# distribution-puissance.net
KiCad netlist of a schematic drawn in EAGLE
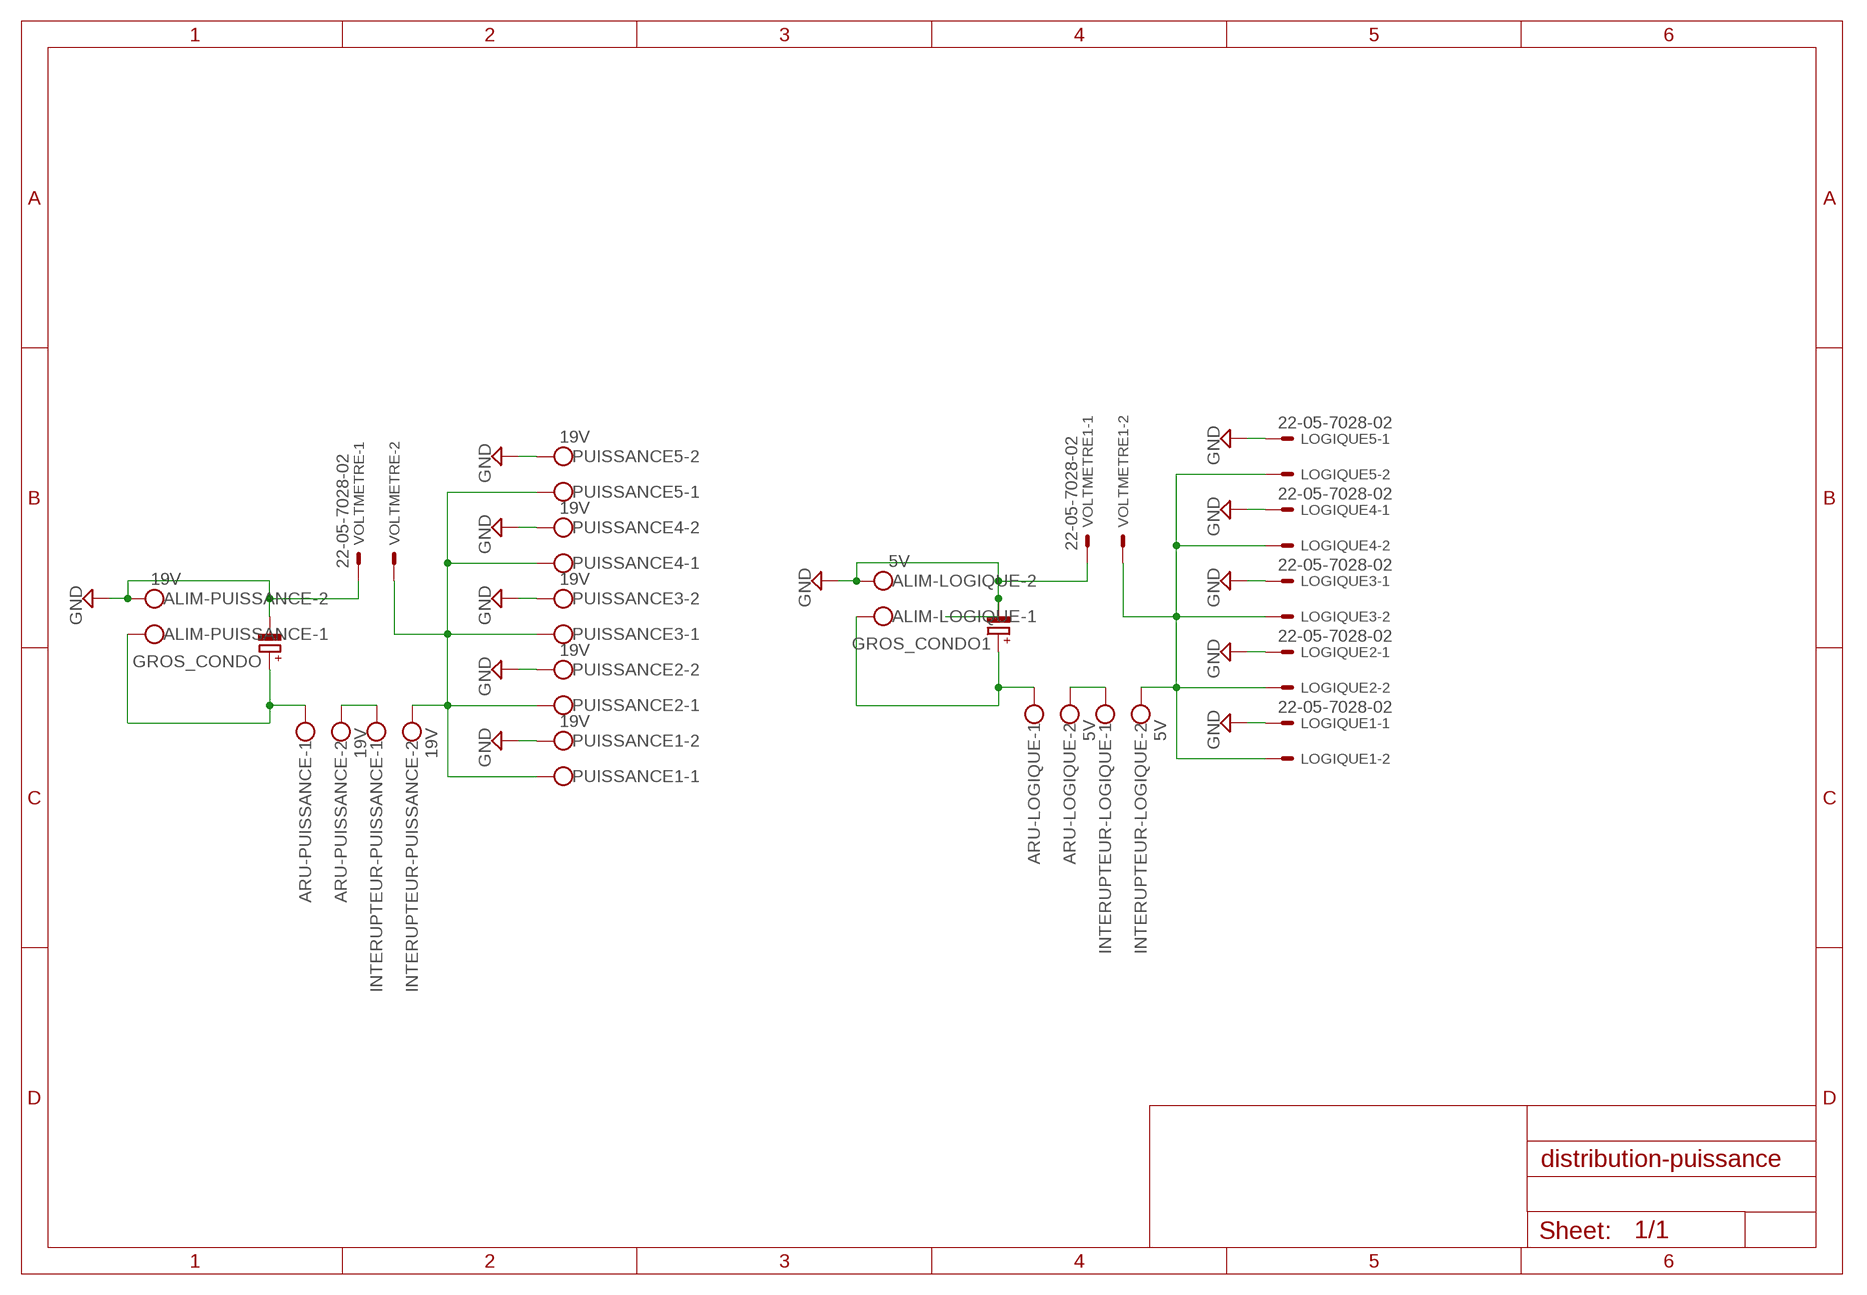
[diagram p0: schematic, sheet 1]

(export (version "E")
  (design (tool "Eeschema 10.0.6"))
  (components
    (comp (ref "ALIM-LOGIQUE")
      (value "5V")
      (footprint "eagle-import:W237-102")
      (fields (field (name "MPN") "237-102"))
      (libsource (lib "eagle-import") (part "W237-102"))
    )
    (comp (ref "ALIM-PUISSANCE")
      (value "19V")
      (footprint "eagle-import:W237-102")
      (fields (field (name "MPN") "237-102"))
      (libsource (lib "eagle-import") (part "W237-102"))
    )
    (comp (ref "ARU-LOGIQUE")
      (value "5V")
      (footprint "eagle-import:W237-102")
      (fields (field (name "MPN") "237-102"))
      (libsource (lib "eagle-import") (part "W237-102"))
    )
    (comp (ref "ARU-PUISSANCE")
      (value "19V")
      (footprint "eagle-import:W237-102")
      (fields (field (name "MPN") "237-102"))
      (libsource (lib "eagle-import") (part "W237-102"))
    )
    (comp (ref "GROS_CONDO")
      (value "CPOL-EUE10-22.5")
      (footprint "eagle-import:EB22,5D")
      (libsource (lib "eagle-import") (part "CPOL-EUE10-22.5"))
    )
    (comp (ref "GROS_CONDO1")
      (value "CPOL-EUE10-22.5")
      (footprint "eagle-import:EB22,5D")
      (libsource (lib "eagle-import") (part "CPOL-EUE10-22.5"))
    )
    (comp (ref "INTERUPTEUR-LOGIQUE")
      (value "5V")
      (footprint "eagle-import:W237-102")
      (fields (field (name "MPN") "237-102"))
      (libsource (lib "eagle-import") (part "W237-102"))
    )
    (comp (ref "INTERUPTEUR-PUISSANCE")
      (value "19V")
      (footprint "eagle-import:W237-102")
      (fields (field (name "MPN") "237-102"))
      (libsource (lib "eagle-import") (part "W237-102"))
    )
    (comp (ref "LOGIQUE1")
      (value "22-05-7028-02")
      (footprint "eagle-import:7395-02")
      (libsource (lib "eagle-import") (part "22-?-0205-7028"))
    )
    (comp (ref "LOGIQUE2")
      (value "22-05-7028-02")
      (footprint "eagle-import:7395-02")
      (libsource (lib "eagle-import") (part "22-?-0205-7028"))
    )
    (comp (ref "LOGIQUE3")
      (value "22-05-7028-02")
      (footprint "eagle-import:7395-02")
      (libsource (lib "eagle-import") (part "22-?-0205-7028"))
    )
    (comp (ref "LOGIQUE4")
      (value "22-05-7028-02")
      (footprint "eagle-import:7395-02")
      (libsource (lib "eagle-import") (part "22-?-0205-7028"))
    )
    (comp (ref "LOGIQUE5")
      (value "22-05-7028-02")
      (footprint "eagle-import:7395-02")
      (libsource (lib "eagle-import") (part "22-?-0205-7028"))
    )
    (comp (ref "PUISSANCE1")
      (value "19V")
      (footprint "eagle-import:W237-102")
      (fields (field (name "MPN") "237-102"))
      (libsource (lib "eagle-import") (part "W237-102"))
    )
    (comp (ref "PUISSANCE2")
      (value "19V")
      (footprint "eagle-import:W237-102")
      (fields (field (name "MPN") "237-102"))
      (libsource (lib "eagle-import") (part "W237-102"))
    )
    (comp (ref "PUISSANCE3")
      (value "19V")
      (footprint "eagle-import:W237-102")
      (fields (field (name "MPN") "237-102"))
      (libsource (lib "eagle-import") (part "W237-102"))
    )
    (comp (ref "PUISSANCE4")
      (value "19V")
      (footprint "eagle-import:W237-102")
      (fields (field (name "MPN") "237-102"))
      (libsource (lib "eagle-import") (part "W237-102"))
    )
    (comp (ref "PUISSANCE5")
      (value "19V")
      (footprint "eagle-import:W237-102")
      (fields (field (name "MPN") "237-102"))
      (libsource (lib "eagle-import") (part "W237-102"))
    )
    (comp (ref "VOLTMETRE")
      (value "22-05-7028-02")
      (footprint "eagle-import:7395-02")
      (libsource (lib "eagle-import") (part "22-?-0205-7028"))
    )
    (comp (ref "VOLTMETRE1")
      (value "22-05-7028-02")
      (footprint "eagle-import:7395-02")
      (libsource (lib "eagle-import") (part "22-?-0205-7028"))
    )
  )
  (nets
    (net (code "1") (name "GND") (class "Default")
      (node (ref "ALIM-LOGIQUE") (pin "2") (pinfunction "KL_2") (pintype "passive"))
      (node (ref "ALIM-PUISSANCE") (pin "2") (pinfunction "KL_2") (pintype "passive"))
      (node (ref "GROS_CONDO") (pin "-") (pinfunction "-_-") (pintype "passive"))
      (node (ref "GROS_CONDO1") (pin "-") (pinfunction "-_-") (pintype "passive"))
      (node (ref "LOGIQUE1") (pin "1") (pinfunction "S_1") (pintype "passive"))
      (node (ref "LOGIQUE2") (pin "1") (pinfunction "S_1") (pintype "passive"))
      (node (ref "LOGIQUE3") (pin "1") (pinfunction "S_1") (pintype "passive"))
      (node (ref "LOGIQUE4") (pin "1") (pinfunction "S_1") (pintype "passive"))
      (node (ref "LOGIQUE5") (pin "1") (pinfunction "S_1") (pintype "passive"))
      (node (ref "PUISSANCE1") (pin "2") (pinfunction "KL_2") (pintype "passive"))
      (node (ref "PUISSANCE2") (pin "2") (pinfunction "KL_2") (pintype "passive"))
      (node (ref "PUISSANCE3") (pin "2") (pinfunction "KL_2") (pintype "passive"))
      (node (ref "PUISSANCE4") (pin "2") (pinfunction "KL_2") (pintype "passive"))
      (node (ref "PUISSANCE5") (pin "2") (pinfunction "KL_2") (pintype "passive"))
      (node (ref "VOLTMETRE") (pin "1") (pinfunction "S_1") (pintype "passive"))
      (node (ref "VOLTMETRE1") (pin "1") (pinfunction "S_1") (pintype "passive"))
    )
    (net (code "2") (name "Net-(ALIM-LOGIQUEA-KL)") (class "Default")
      (node (ref "ALIM-LOGIQUE") (pin "1") (pinfunction "KL_1") (pintype "passive"))
      (node (ref "ARU-LOGIQUE") (pin "1") (pinfunction "KL_1") (pintype "passive"))
      (node (ref "GROS_CONDO1") (pin "+") (pinfunction "+_+") (pintype "passive"))
    )
    (net (code "3") (name "Net-(ALIM-PUISSANCEA-KL)") (class "Default")
      (node (ref "ALIM-PUISSANCE") (pin "1") (pinfunction "KL_1") (pintype "passive"))
      (node (ref "ARU-PUISSANCE") (pin "1") (pinfunction "KL_1") (pintype "passive"))
      (node (ref "GROS_CONDO") (pin "+") (pinfunction "+_+") (pintype "passive"))
    )
    (net (code "4") (name "Net-(ARU-LOGIQUEB-KL)") (class "Default")
      (node (ref "ARU-LOGIQUE") (pin "2") (pinfunction "KL_2") (pintype "passive"))
      (node (ref "INTERUPTEUR-LOGIQUE") (pin "1") (pinfunction "KL_1") (pintype "passive"))
    )
    (net (code "5") (name "Net-(ARU-PUISSANCEB-KL)") (class "Default")
      (node (ref "ARU-PUISSANCE") (pin "2") (pinfunction "KL_2") (pintype "passive"))
      (node (ref "INTERUPTEUR-PUISSANCE") (pin "1") (pinfunction "KL_1") (pintype "passive"))
    )
    (net (code "6") (name "Net-(INTERUPTEUR-LOGIQUEB-KL)") (class "Default")
      (node (ref "INTERUPTEUR-LOGIQUE") (pin "2") (pinfunction "KL_2") (pintype "passive"))
      (node (ref "LOGIQUE1") (pin "2") (pinfunction "S_2") (pintype "passive"))
      (node (ref "LOGIQUE2") (pin "2") (pinfunction "S_2") (pintype "passive"))
      (node (ref "LOGIQUE3") (pin "2") (pinfunction "S_2") (pintype "passive"))
      (node (ref "LOGIQUE4") (pin "2") (pinfunction "S_2") (pintype "passive"))
      (node (ref "LOGIQUE5") (pin "2") (pinfunction "S_2") (pintype "passive"))
      (node (ref "VOLTMETRE1") (pin "2") (pinfunction "S_2") (pintype "passive"))
    )
    (net (code "7") (name "Net-(INTERUPTEUR-PUISSANCEB-KL)") (class "Default")
      (node (ref "INTERUPTEUR-PUISSANCE") (pin "2") (pinfunction "KL_2") (pintype "passive"))
      (node (ref "PUISSANCE1") (pin "1") (pinfunction "KL_1") (pintype "passive"))
      (node (ref "PUISSANCE2") (pin "1") (pinfunction "KL_1") (pintype "passive"))
      (node (ref "PUISSANCE3") (pin "1") (pinfunction "KL_1") (pintype "passive"))
      (node (ref "PUISSANCE4") (pin "1") (pinfunction "KL_1") (pintype "passive"))
      (node (ref "PUISSANCE5") (pin "1") (pinfunction "KL_1") (pintype "passive"))
      (node (ref "VOLTMETRE") (pin "2") (pinfunction "S_2") (pintype "passive"))
    )
  )
)
